# rev3.net
KiCad netlist of a schematic drawn in EAGLE
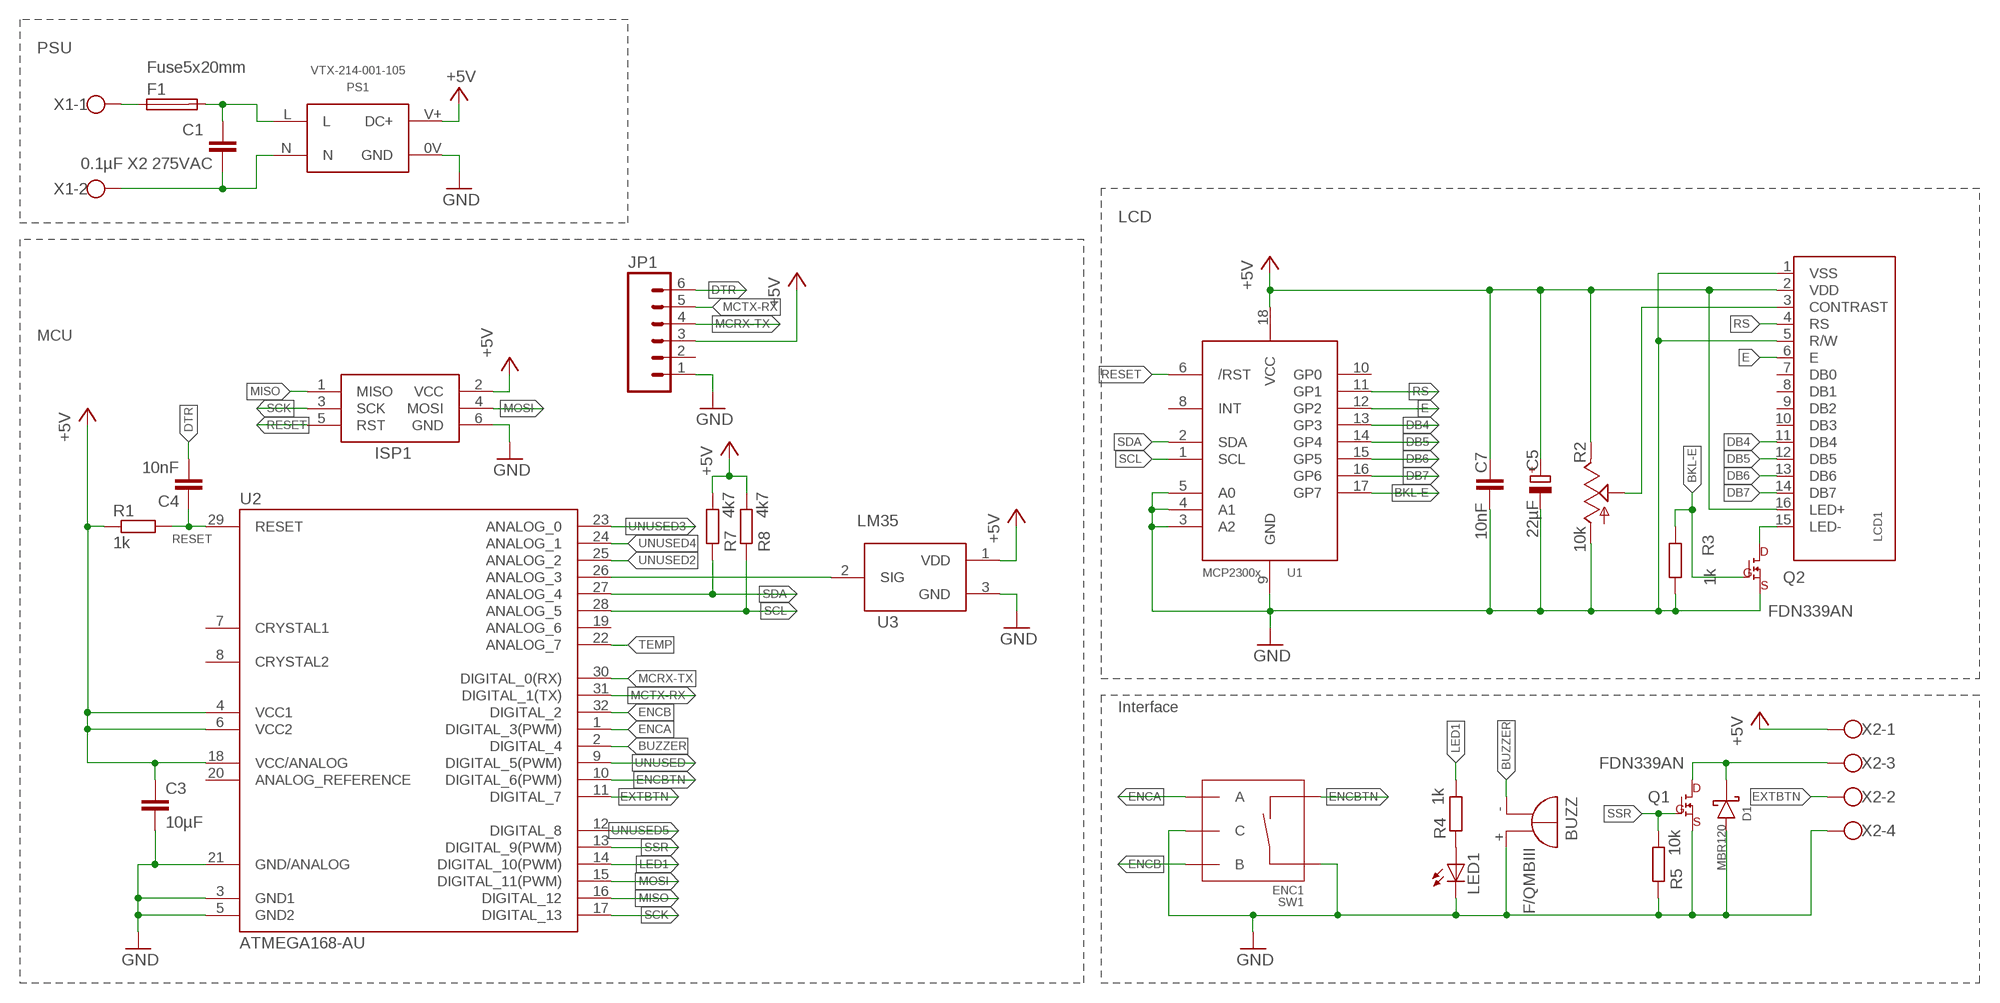
[diagram p0: schematic, sheet 1]

(export (version "E")
  (design (tool "Eeschema 10.0.6"))
  (components
    (comp (ref "BUZZ")
      (value "F/QMBIII")
      (footprint "eagle-import:F_QMBIII")
      (libsource (lib "eagle-import") (part "F/QMBIII"))
    )
    (comp (ref "C1")
      (value "0.1µF X2 275VAC")
      (footprint "eagle-import:C102-064X133")
      (libsource (lib "eagle-import") (part "C-EU102-064X133"))
    )
    (comp (ref "C3")
      (value "10µF")
      (footprint "eagle-import:C3216")
      (libsource (lib "eagle-import") (part "C-EUC3216"))
    )
    (comp (ref "C4")
      (value "10nF")
      (footprint "eagle-import:C1206K")
      (libsource (lib "eagle-import") (part "C-EUC1206K"))
    )
    (comp (ref "C5")
      (value "22µF")
      (footprint "eagle-import:E2,5-6E")
      (libsource (lib "eagle-import") (part "CPOL-EUE2,5-6E"))
    )
    (comp (ref "C7")
      (value "10nF")
      (footprint "eagle-import:C1206K")
      (libsource (lib "eagle-import") (part "C-EUC1206K"))
    )
    (comp (ref "D1")
      (value "MBR120")
      (footprint "eagle-import:SOD-123FL")
      (libsource (lib "eagle-import") (part "MBR120"))
    )
    (comp (ref "F1")
      (value "Fuse5x20mm")
      (footprint "eagle-import:FUSE_HOLDER_5X20MM")
      (libsource (lib "eagle-import") (part "FUSEBLANK_5X20MM"))
    )
    (comp (ref "ISP1")
      (value "AVRISP-6")
      (footprint "eagle-import:AVRISP")
      (libsource (lib "eagle-import") (part "AVRISP-6"))
    )
    (comp (ref "JP1")
      (value "M06LOCK")
      (footprint "eagle-import:1X06_LOCK")
      (libsource (lib "eagle-import") (part "M06LOCK"))
    )
    (comp (ref "LCD1")
      (value "HD44780-LCD")
      (footprint "eagle-import:8X2-CHARLCD")
      (libsource (lib "eagle-import") (part "HD44780-LCD"))
    )
    (comp (ref "LED1")
      (value "LED5MM")
      (footprint "eagle-import:LED5MM")
      (libsource (lib "eagle-import") (part "LED5MM"))
    )
    (comp (ref "PS1")
      (value "VTX-214-001-105")
      (footprint "eagle-import:VTX-214-001-")
      (libsource (lib "eagle-import") (part "VTX-214-001-105"))
    )
    (comp (ref "Q1")
      (value "FDN339AN")
      (footprint "eagle-import:SOT23")
      (libsource (lib "eagle-import") (part "FDN339AN"))
    )
    (comp (ref "Q2")
      (value "FDN339AN")
      (footprint "eagle-import:SOT23")
      (libsource (lib "eagle-import") (part "FDN339AN"))
    )
    (comp (ref "R1")
      (value "1k")
      (footprint "eagle-import:R0603")
      (libsource (lib "eagle-import") (part "R-EU_R0603"))
    )
    (comp (ref "R2")
      (value "10k")
      (footprint "eagle-import:B64Y")
      (libsource (lib "eagle-import") (part "TRIM_US-B64Y"))
    )
    (comp (ref "R3")
      (value "1k")
      (footprint "eagle-import:R0603")
      (libsource (lib "eagle-import") (part "R-EU_R0603"))
    )
    (comp (ref "R4")
      (value "1k")
      (footprint "eagle-import:R0603")
      (libsource (lib "eagle-import") (part "R-EU_R0603"))
    )
    (comp (ref "R5")
      (value "10k")
      (footprint "eagle-import:R0603")
      (libsource (lib "eagle-import") (part "R-EU_R0603"))
    )
    (comp (ref "R7")
      (value "4k7")
      (footprint "eagle-import:R0603")
      (libsource (lib "eagle-import") (part "R-EU_R0603"))
    )
    (comp (ref "R8")
      (value "4k7")
      (footprint "eagle-import:R0603")
      (libsource (lib "eagle-import") (part "R-EU_R0603"))
    )
    (comp (ref "SW1")
      (value "ENC1")
      (footprint "eagle-import:ROTARY_ENC_PLAIN")
      (libsource (lib "eagle-import") (part "ROTARTY_ENCODER"))
    )
    (comp (ref "U1")
      (value "MCP2300X/SO")
      (footprint "eagle-import:SO18W")
      (libsource (lib "eagle-import") (part "MCP2300X/SO"))
    )
    (comp (ref "U2")
      (value "ATMEGA168-AU")
      (footprint "eagle-import:TQFP32-08")
      (libsource (lib "eagle-import") (part "ATMEGA168-AU"))
    )
    (comp (ref "U3")
      (value "LM35")
      (footprint "eagle-import:TO92-")
      (libsource (lib "eagle-import") (part "LM35"))
    )
    (comp (ref "X1")
      (value "W237-113")
      (footprint "eagle-import:W237-113")
      (libsource (lib "eagle-import") (part "W237-113"))
    )
    (comp (ref "X2")
      (value "W237-4")
      (footprint "eagle-import:W237-4")
      (libsource (lib "eagle-import") (part "W237-4"))
    )
  )
  (nets
    (net (code "1") (name "+5V") (class "Default")
      (node (ref "C3") (pin "1") (pinfunction "1_1") (pintype "passive"))
      (node (ref "C5") (pin "+") (pinfunction "+_+") (pintype "passive"))
      (node (ref "C7") (pin "1") (pinfunction "1_1") (pintype "passive"))
      (node (ref "ISP1") (pin "2") (pinfunction "VCC_2") (pintype "power_in"))
      (node (ref "JP1") (pin "3") (pinfunction "3_3") (pintype "passive"))
      (node (ref "LCD1") (pin "16") (pinfunction "LED+_16") (pintype "power_in"))
      (node (ref "LCD1") (pin "2") (pinfunction "VDD_2") (pintype "power_in"))
      (node (ref "PS1") (pin "V+") (pinfunction "DC+_V+") (pintype "bidirectional"))
      (node (ref "R1") (pin "1") (pinfunction "1_1") (pintype "passive"))
      (node (ref "R2") (pin "E") (pinfunction "E_E") (pintype "passive"))
      (node (ref "R7") (pin "2") (pinfunction "2_2") (pintype "passive"))
      (node (ref "R8") (pin "2") (pinfunction "2_2") (pintype "passive"))
      (node (ref "U1") (pin "18") (pinfunction "VCC_18") (pintype "power_in"))
      (node (ref "U2") (pin "18") (pinfunction "VCC/ANALOG_18") (pintype "passive"))
      (node (ref "U2") (pin "4") (pinfunction "VCC1_4") (pintype "power_in"))
      (node (ref "U2") (pin "6") (pinfunction "VCC2_6") (pintype "power_in"))
      (node (ref "U3") (pin "1") (pinfunction "VDD_1") (pintype "bidirectional"))
      (node (ref "X2") (pin "1") (pinfunction "KL_1") (pintype "passive"))
    )
    (net (code "2") (name "BKL-E") (class "Default")
      (node (ref "Q2") (pin "1") (pinfunction "GATE_1") (pintype "bidirectional"))
      (node (ref "R3") (pin "1") (pinfunction "1_1") (pintype "passive"))
      (node (ref "U1") (pin "17") (pinfunction "GP7_17") (pintype "bidirectional"))
    )
    (net (code "3") (name "BUZZER") (class "Default")
      (node (ref "BUZZ") (pin "-") (pinfunction "+_-") (pintype "passive"))
      (node (ref "U2") (pin "2") (pinfunction "DIGITAL_4_2") (pintype "bidirectional"))
    )
    (net (code "4") (name "DB4") (class "Default")
      (node (ref "LCD1") (pin "11") (pinfunction "DB4_11") (pintype "input"))
      (node (ref "U1") (pin "13") (pinfunction "GP3_13") (pintype "bidirectional"))
    )
    (net (code "5") (name "DB5") (class "Default")
      (node (ref "LCD1") (pin "12") (pinfunction "DB5_12") (pintype "input"))
      (node (ref "U1") (pin "14") (pinfunction "GP4_14") (pintype "bidirectional"))
    )
    (net (code "6") (name "DB6") (class "Default")
      (node (ref "LCD1") (pin "13") (pinfunction "DB6_13") (pintype "input"))
      (node (ref "U1") (pin "15") (pinfunction "GP5_15") (pintype "bidirectional"))
    )
    (net (code "7") (name "DB7") (class "Default")
      (node (ref "LCD1") (pin "14") (pinfunction "DB7_14") (pintype "input"))
      (node (ref "U1") (pin "16") (pinfunction "GP6_16") (pintype "bidirectional"))
    )
    (net (code "8") (name "DTR") (class "Default")
      (node (ref "C4") (pin "2") (pinfunction "2_2") (pintype "passive"))
      (node (ref "JP1") (pin "6") (pinfunction "6_6") (pintype "passive"))
    )
    (net (code "9") (name "E") (class "Default")
      (node (ref "LCD1") (pin "6") (pinfunction "E_6") (pintype "input"))
      (node (ref "U1") (pin "12") (pinfunction "GP2_12") (pintype "bidirectional"))
    )
    (net (code "10") (name "ENCA") (class "Default")
      (node (ref "SW1") (pin "A") (pinfunction "A_A") (pintype "bidirectional"))
      (node (ref "U2") (pin "1") (pinfunction "DIGITAL_3(PWM)_1") (pintype "bidirectional"))
    )
    (net (code "11") (name "ENCB") (class "Default")
      (node (ref "SW1") (pin "B") (pinfunction "B_B") (pintype "bidirectional"))
      (node (ref "U2") (pin "32") (pinfunction "DIGITAL_2_32") (pintype "bidirectional"))
    )
    (net (code "12") (name "ENCBTN") (class "Default")
      (node (ref "SW1") (pin "SW-") (pinfunction "SW-_SW-") (pintype "bidirectional"))
      (node (ref "U2") (pin "10") (pinfunction "DIGITAL_6(PWM)_10") (pintype "bidirectional"))
    )
    (net (code "13") (name "EXTBTN") (class "Default")
      (node (ref "U2") (pin "11") (pinfunction "DIGITAL_7_11") (pintype "bidirectional"))
      (node (ref "X2") (pin "2") (pinfunction "KL_2") (pintype "passive"))
    )
    (net (code "14") (name "GND") (class "Default")
      (node (ref "BUZZ") (pin "+") (pinfunction "-_+") (pintype "passive"))
      (node (ref "C3") (pin "2") (pinfunction "2_2") (pintype "passive"))
      (node (ref "C5") (pin "-") (pinfunction "-_-") (pintype "passive"))
      (node (ref "C7") (pin "2") (pinfunction "2_2") (pintype "passive"))
      (node (ref "D1") (pin "A") (pinfunction "A_A") (pintype "bidirectional"))
      (node (ref "ISP1") (pin "6") (pinfunction "GND_6") (pintype "power_in"))
      (node (ref "JP1") (pin "1") (pinfunction "1_1") (pintype "passive"))
      (node (ref "LCD1") (pin "1") (pinfunction "VSS_1") (pintype "power_in"))
      (node (ref "LCD1") (pin "5") (pinfunction "R/W_5") (pintype "input"))
      (node (ref "LED1") (pin "K") (pinfunction "C_K") (pintype "passive"))
      (node (ref "PS1") (pin "0V") (pinfunction "GND_0V") (pintype "bidirectional"))
      (node (ref "Q1") (pin "2") (pinfunction "SOURCE_2") (pintype "bidirectional"))
      (node (ref "Q2") (pin "2") (pinfunction "SOURCE_2") (pintype "bidirectional"))
      (node (ref "R2") (pin "A") (pinfunction "A_A") (pintype "passive"))
      (node (ref "R3") (pin "2") (pinfunction "2_2") (pintype "passive"))
      (node (ref "R5") (pin "1") (pinfunction "1_1") (pintype "passive"))
      (node (ref "SW1") (pin "C") (pinfunction "C_C") (pintype "bidirectional"))
      (node (ref "SW1") (pin "SW+") (pinfunction "SW+_SW+") (pintype "bidirectional"))
      (node (ref "U1") (pin "3") (pinfunction "A2_3") (pintype "input"))
      (node (ref "U1") (pin "4") (pinfunction "A1_4") (pintype "input"))
      (node (ref "U1") (pin "5") (pinfunction "A0_5") (pintype "input"))
      (node (ref "U1") (pin "9") (pinfunction "GND_9") (pintype "power_in"))
      (node (ref "U2") (pin "21") (pinfunction "GND/ANALOG_21") (pintype "power_in"))
      (node (ref "U2") (pin "3") (pinfunction "GND1_3") (pintype "power_in"))
      (node (ref "U2") (pin "5") (pinfunction "GND2_5") (pintype "power_in"))
      (node (ref "U3") (pin "3") (pinfunction "GND_3") (pintype "bidirectional"))
      (node (ref "X2") (pin "4") (pinfunction "KL_4") (pintype "passive"))
    )
    (net (code "15") (name "LED1") (class "Default")
      (node (ref "R4") (pin "2") (pinfunction "2_2") (pintype "passive"))
      (node (ref "U2") (pin "14") (pinfunction "DIGITAL_10(PWM)_14") (pintype "bidirectional"))
    )
    (net (code "16") (name "MCRX-TX") (class "Default")
      (node (ref "JP1") (pin "4") (pinfunction "4_4") (pintype "passive"))
      (node (ref "U2") (pin "30") (pinfunction "DIGITAL_0(RX)_30") (pintype "bidirectional"))
    )
    (net (code "17") (name "MCTX-RX") (class "Default")
      (node (ref "JP1") (pin "5") (pinfunction "5_5") (pintype "passive"))
      (node (ref "U2") (pin "31") (pinfunction "DIGITAL_1(TX)_31") (pintype "bidirectional"))
    )
    (net (code "18") (name "MISO") (class "Default")
      (node (ref "ISP1") (pin "1") (pinfunction "MISO_1") (pintype "input"))
      (node (ref "U2") (pin "16") (pinfunction "DIGITAL_12_16") (pintype "bidirectional"))
    )
    (net (code "19") (name "MOSI") (class "Default")
      (node (ref "ISP1") (pin "4") (pinfunction "MOSI_4") (pintype "output"))
      (node (ref "U2") (pin "15") (pinfunction "DIGITAL_11(PWM)_15") (pintype "bidirectional"))
    )
    (net (code "20") (name "Net-(C1-Pad1)") (class "Default")
      (node (ref "C1") (pin "1") (pinfunction "1_1") (pintype "passive"))
      (node (ref "F1") (pin "2") (pinfunction "2_2") (pintype "passive"))
      (node (ref "PS1") (pin "L") (pinfunction "L_L") (pintype "bidirectional"))
    )
    (net (code "21") (name "Net-(LCD1-CONTRAST)") (class "Default")
      (node (ref "LCD1") (pin "3") (pinfunction "CONTRAST_3") (pintype "input"))
      (node (ref "R2") (pin "S") (pinfunction "S_S") (pintype "passive"))
    )
    (net (code "22") (name "Net-(LCD1-LED-)") (class "Default")
      (node (ref "LCD1") (pin "15") (pinfunction "LED-_15") (pintype "power_in"))
      (node (ref "Q2") (pin "3") (pinfunction "DRAIN_3") (pintype "bidirectional"))
    )
    (net (code "23") (name "Net-(LED1-PadA)") (class "Default")
      (node (ref "LED1") (pin "A") (pinfunction "A_A") (pintype "passive"))
      (node (ref "R4") (pin "1") (pinfunction "1_1") (pintype "passive"))
    )
    (net (code "24") (name "Net-(Q1-DRAIN)") (class "Default")
      (node (ref "D1") (pin "C") (pinfunction "C_C") (pintype "bidirectional"))
      (node (ref "Q1") (pin "3") (pinfunction "DRAIN_3") (pintype "bidirectional"))
      (node (ref "X2") (pin "3") (pinfunction "KL_3") (pintype "passive"))
    )
    (net (code "25") (name "Net-(U2-ANALOG_3)") (class "Default")
      (node (ref "U2") (pin "26") (pinfunction "ANALOG_3_26") (pintype "bidirectional"))
      (node (ref "U3") (pin "2") (pinfunction "SIG_2") (pintype "bidirectional"))
    )
    (net (code "26") (name "Net-(X1A-KL)") (class "Default")
      (node (ref "F1") (pin "1") (pinfunction "1_1") (pintype "passive"))
      (node (ref "X1") (pin "1") (pinfunction "KL_1") (pintype "passive"))
    )
    (net (code "27") (name "Net-(X1B-KL)") (class "Default")
      (node (ref "C1") (pin "2") (pinfunction "2_2") (pintype "passive"))
      (node (ref "PS1") (pin "N") (pinfunction "N_N") (pintype "bidirectional"))
      (node (ref "X1") (pin "2") (pinfunction "KL_2") (pintype "passive"))
    )
    (net (code "28") (name "RESET") (class "Default")
      (node (ref "C4") (pin "1") (pinfunction "1_1") (pintype "passive"))
      (node (ref "ISP1") (pin "5") (pinfunction "RST_5") (pintype "output"))
      (node (ref "R1") (pin "2") (pinfunction "2_2") (pintype "passive"))
      (node (ref "U1") (pin "6") (pinfunction "/RST_6") (pintype "input"))
      (node (ref "U2") (pin "29") (pinfunction "RESET_29") (pintype "bidirectional"))
    )
    (net (code "29") (name "RS") (class "Default")
      (node (ref "LCD1") (pin "4") (pinfunction "RS_4") (pintype "input"))
      (node (ref "U1") (pin "11") (pinfunction "GP1_11") (pintype "bidirectional"))
    )
    (net (code "30") (name "SCK") (class "Default")
      (node (ref "ISP1") (pin "3") (pinfunction "SCK_3") (pintype "output"))
      (node (ref "U2") (pin "17") (pinfunction "DIGITAL_13_17") (pintype "bidirectional"))
    )
    (net (code "31") (name "SCL") (class "Default")
      (node (ref "R8") (pin "1") (pinfunction "1_1") (pintype "passive"))
      (node (ref "U1") (pin "1") (pinfunction "SCL_1") (pintype "bidirectional"))
      (node (ref "U2") (pin "28") (pinfunction "ANALOG_5_28") (pintype "bidirectional"))
    )
    (net (code "32") (name "SDA") (class "Default")
      (node (ref "R7") (pin "1") (pinfunction "1_1") (pintype "passive"))
      (node (ref "U1") (pin "2") (pinfunction "SDA_2") (pintype "bidirectional"))
      (node (ref "U2") (pin "27") (pinfunction "ANALOG_4_27") (pintype "bidirectional"))
    )
    (net (code "33") (name "SSR") (class "Default")
      (node (ref "Q1") (pin "1") (pinfunction "GATE_1") (pintype "bidirectional"))
      (node (ref "R5") (pin "2") (pinfunction "2_2") (pintype "passive"))
      (node (ref "U2") (pin "13") (pinfunction "DIGITAL_9(PWM)_13") (pintype "bidirectional"))
    )
    (net (code "34") (name "TEMP") (class "Default")
      (node (ref "U2") (pin "22") (pinfunction "ANALOG_7_22") (pintype "passive"))
    )
    (net (code "35") (name "UNUSED") (class "Default")
      (node (ref "U2") (pin "9") (pinfunction "DIGITAL_5(PWM)_9") (pintype "bidirectional"))
    )
    (net (code "36") (name "UNUSED2") (class "Default")
      (node (ref "U2") (pin "25") (pinfunction "ANALOG_2_25") (pintype "bidirectional"))
    )
    (net (code "37") (name "UNUSED3") (class "Default")
      (node (ref "U2") (pin "23") (pinfunction "ANALOG_0_23") (pintype "bidirectional"))
    )
    (net (code "38") (name "UNUSED4") (class "Default")
      (node (ref "U2") (pin "24") (pinfunction "ANALOG_1_24") (pintype "bidirectional"))
    )
    (net (code "39") (name "UNUSED5") (class "Default")
      (node (ref "U2") (pin "12") (pinfunction "DIGITAL_8_12") (pintype "bidirectional"))
    )
    (net (code "40") (name "unconnected-(JP1-Pad2)") (class "Default")
      (node (ref "JP1") (pin "2") (pinfunction "2_2") (pintype "passive"))
    )
    (net (code "41") (name "unconnected-(LCD1-DB0-Pad7)") (class "Default")
      (node (ref "LCD1") (pin "7") (pinfunction "DB0_7") (pintype "input"))
    )
    (net (code "42") (name "unconnected-(LCD1-DB1-Pad8)") (class "Default")
      (node (ref "LCD1") (pin "8") (pinfunction "DB1_8") (pintype "input"))
    )
    (net (code "43") (name "unconnected-(LCD1-DB2-Pad9)") (class "Default")
      (node (ref "LCD1") (pin "9") (pinfunction "DB2_9") (pintype "input"))
    )
    (net (code "44") (name "unconnected-(LCD1-DB3-Pad10)") (class "Default")
      (node (ref "LCD1") (pin "10") (pinfunction "DB3_10") (pintype "input"))
    )
    (net (code "45") (name "unconnected-(U1-GP0-Pad10)") (class "Default")
      (node (ref "U1") (pin "10") (pinfunction "GP0_10") (pintype "bidirectional"))
    )
    (net (code "46") (name "unconnected-(U1-INT-Pad8)") (class "Default")
      (node (ref "U1") (pin "8") (pinfunction "INT_8") (pintype "output"))
    )
    (net (code "47") (name "unconnected-(U2-ANALOG_6-Pad19)") (class "Default")
      (node (ref "U2") (pin "19") (pinfunction "ANALOG_6_19") (pintype "passive"))
    )
    (net (code "48") (name "unconnected-(U2-ANALOG_REFERENCE-Pad20)") (class "Default")
      (node (ref "U2") (pin "20") (pinfunction "ANALOG_REFERENCE_20") (pintype "passive"))
    )
    (net (code "49") (name "unconnected-(U2-CRYSTAL1-Pad7)") (class "Default")
      (node (ref "U2") (pin "7") (pinfunction "CRYSTAL1_7") (pintype "bidirectional"))
    )
    (net (code "50") (name "unconnected-(U2-CRYSTAL2-Pad8)") (class "Default")
      (node (ref "U2") (pin "8") (pinfunction "CRYSTAL2_8") (pintype "bidirectional"))
    )
  )
)
